# MCU098_06_XDS110-ET_USB_Power.net
KiCad netlist of a schematic drawn in Altium Designer
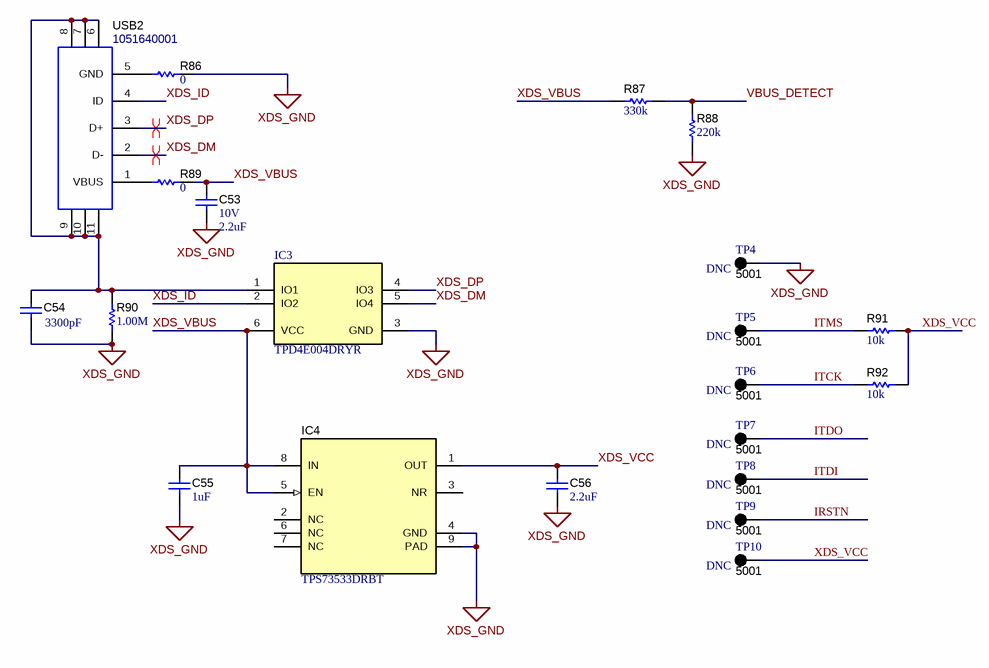
[diagram p0: MCU098_06_XDS110-ET_USB_Power.SchDoc]

(export (version "E")
  (design (tool "Eeschema 10.0.6"))
  (components
    (comp (ref "C53")
      (value "C0603C225K8PACTU")
      (footprint "0603")
      (description "CAP, CERM, 2.2 uF, 10 V, +/- 10%, X5R, 0603")
      (fields
        (field (name "MANUFACTURER") "Kemet")
        (field (name "VDC_V") "10V")
        (field (name "VALUEDISPLAYED") "2.2uF")
        (field (name "PUBLISHER") "Texas Instruments")
      )
      (libsource (lib "Altium Vault - TI") (part "Capacitor"))
    )
    (comp (ref "C54")
      (value "GRM155R71H332KA01D")
      (footprint "0402")
      (description "CAP, CERM, 3300 pF, 50 V, +/- 10%, X7R, 0402")
      (fields
        (field (name "MANUFACTURER") "MuRata")
        (field (name "VALUEDISPLAYED") "3300pF")
        (field (name "PUBLISHER") "Texas Instruments")
      )
      (libsource (lib "Altium Vault - TI") (part "Capacitor"))
    )
    (comp (ref "C55")
      (value "C1005X5R1E105K050BC")
      (footprint "0402")
      (description "CAP, CERM, 1 uF, 25 V, +/- 10%, X5R, 0402")
      (fields
        (field (name "MANUFACTURER") "TDK")
        (field (name "VALUEDISPLAYED") "1uF")
        (field (name "PUBLISHER") "Texas Instruments")
      )
      (libsource (lib "Altium Vault - TI") (part "Capacitor"))
    )
    (comp (ref "C56")
      (value "GRM155R60J225KE95D")
      (footprint "0402")
      (description "CAP, CERM, 2.2 uF, 6.3 V, +/- 10%, X5R, 0402")
      (fields
        (field (name "MANUFACTURER") "MuRata")
        (field (name "VALUEDISPLAYED") "2.2uF")
        (field (name "PUBLISHER") "Texas Instruments")
      )
      (libsource (lib "Altium Vault - TI") (part "Capacitor"))
    )
    (comp (ref "IC3")
      (value "TPD4E004DRYR")
      (footprint "DRY0006A")
      (fields (field (name "MANUFACTURER") "Texas Instruments") (field (name "PARTNUMBER") "TPD4E004DRYR"))
      (libsource (lib "Altium Vault - TI") (part "TI-TPD4E004-SON_DRY-6"))
    )
    (comp (ref "IC4")
      (value "TPS73533DRBT")
      (footprint "DRB0008A")
      (fields (field (name "MANUFACTURER") "Texas Instruments") (field (name "PARTNUMBER") "TPS73533DRBT"))
      (libsource (lib "Altium Vault - TI") (part "TPS735xxDRB"))
    )
    (comp (ref "R86")
      (value "RC0603JR-070RL")
      (footprint "0603")
      (description "RES, 0, 5%, 0.1 W, 0603")
      (fields (field (name "MANUFACTURER") "Yageo") (field (name "VALUEDISPLAYED") "0"))
      (libsource (lib "Altium Vault - TI") (part "Resistor"))
    )
    (comp (ref "R87")
      (value "RC0402FR-07330KL")
      (footprint "0402")
      (description "RES, 330 k, 1%, 0.0625 W, 0402")
      (fields
        (field (name "MANUFACTURER") "Yageo America")
        (field (name "VALUEDISPLAYED") "330k")
        (field (name "PUBLISHER") "Texas Instruments")
      )
      (libsource (lib "Altium Vault - TI") (part "Resistor"))
    )
    (comp (ref "R88")
      (value "RC0402FR-07220KL")
      (footprint "0402")
      (description "RES, 220 k, 1%, 0.0625 W, 0402")
      (fields
        (field (name "MANUFACTURER") "Yageo America")
        (field (name "VALUEDISPLAYED") "220k")
        (field (name "PUBLISHER") "Texas Instruments")
      )
      (libsource (lib "Altium Vault - TI") (part "Resistor"))
    )
    (comp (ref "R89")
      (value "RC0603JR-070RL")
      (footprint "0603")
      (description "RES, 0, 5%, 0.1 W, 0603")
      (fields (field (name "MANUFACTURER") "Yageo") (field (name "VALUEDISPLAYED") "0"))
      (libsource (lib "Altium Vault - TI") (part "Resistor"))
    )
    (comp (ref "R90")
      (value "CRCW04021M00FKED")
      (footprint "0402")
      (description "RES, 1.00 M, 1%, 0.063 W, 0402")
      (fields
        (field (name "MANUFACTURER") "Vishay-Dale")
        (field (name "VALUEDISPLAYED") "1.00M")
        (field (name "PUBLISHER") "Texas Instruments")
      )
      (libsource (lib "Altium Vault - TI") (part "Resistor"))
    )
    (comp (ref "R91")
      (value "CRCW040210K0JNED")
      (footprint "0402")
      (description "RES, 10 k, 5%, 0.063 W, 0402")
      (fields
        (field (name "MANUFACTURER") "Vishay-Dale")
        (field (name "VALUEDISPLAYED") "10k")
        (field (name "PUBLISHER") "Texas Instruments")
      )
      (libsource (lib "Altium Vault - TI") (part "Resistor"))
    )
    (comp (ref "R92")
      (value "CRCW040210K0JNED")
      (footprint "0402")
      (description "RES, 10 k, 5%, 0.063 W, 0402")
      (fields
        (field (name "MANUFACTURER") "Vishay-Dale")
        (field (name "VALUEDISPLAYED") "10k")
        (field (name "PUBLISHER") "Texas Instruments")
      )
      (libsource (lib "Altium Vault - TI") (part "Resistor"))
    )
    (comp (ref "TP4")
      (value "5001")
      (footprint "Keystone5001")
      (description "Test Point, Miniature, Black, TH")
      (fields
        (field (name "MANUFACTURER") "Keystone")
        (field (name "DISPLAY") "DNC")
        (field (name "PUBLISHER") "Texas Instruments")
      )
      (libsource (lib "Altium Vault - TI") (part "5001"))
    )
    (comp (ref "TP5")
      (value "5001")
      (footprint "Keystone5001")
      (description "Test Point, Miniature, Black, TH")
      (fields
        (field (name "MANUFACTURER") "Keystone")
        (field (name "DISPALY") "DNC")
        (field (name "PUBLISHER") "Texas Instruments")
      )
      (libsource (lib "Altium Vault - TI") (part "5001"))
    )
    (comp (ref "TP6")
      (value "5001")
      (footprint "Keystone5001")
      (description "Test Point, Miniature, Black, TH")
      (fields
        (field (name "MANUFACTURER") "Keystone")
        (field (name "DISPALY") "DNC")
        (field (name "PUBLISHER") "Texas Instruments")
      )
      (libsource (lib "Altium Vault - TI") (part "5001"))
    )
    (comp (ref "TP7")
      (value "5001")
      (footprint "Keystone5001")
      (description "Test Point, Miniature, Black, TH")
      (fields
        (field (name "MANUFACTURER") "Keystone")
        (field (name "DISPALY") "DNC")
        (field (name "PUBLISHER") "Texas Instruments")
      )
      (libsource (lib "Altium Vault - TI") (part "5001"))
    )
    (comp (ref "TP8")
      (value "5001")
      (footprint "Keystone5001")
      (description "Test Point, Miniature, Black, TH")
      (fields
        (field (name "MANUFACTURER") "Keystone")
        (field (name "DISPALY") "DNC")
        (field (name "PUBLISHER") "Texas Instruments")
      )
      (libsource (lib "Altium Vault - TI") (part "5001"))
    )
    (comp (ref "TP9")
      (value "5001")
      (footprint "Keystone5001")
      (description "Test Point, Miniature, Black, TH")
      (fields
        (field (name "MANUFACTURER") "Keystone")
        (field (name "DISPALY") "DNC")
        (field (name "PUBLISHER") "Texas Instruments")
      )
      (libsource (lib "Altium Vault - TI") (part "5001"))
    )
    (comp (ref "TP10")
      (value "5001")
      (footprint "Keystone5001")
      (description "Test Point, Miniature, Black, TH")
      (fields
        (field (name "MANUFACTURER") "Keystone")
        (field (name "DISPALY") "DNC")
        (field (name "PUBLISHER") "Texas Instruments")
      )
      (libsource (lib "Altium Vault - TI") (part "5001"))
    )
    (comp (ref "USB2")
      (value "1051640001")
      (footprint "Molex_1051640001")
      (description "Receptacle, USB 2.0, Micro B, 5 Position, R/A, SMT")
      (fields (field (name "MANUFACTURER") "Molex") (field (name "PUBLISHER") "Texas Instruments"))
      (libsource (lib "Altium Vault - TI") (part "CONN_USB_MicroMini_6Shld"))
    )
  )
  (nets
    (net (code "1") (name "/IRSTN") (class "Default") (node (ref "TP9") (pin "1") (pintype "passive")))
    (net (code "2") (name "/ITCK") (class "Default")
      (node (ref "R92") (pin "2") (pinfunction "2_2") (pintype "passive"))
      (node (ref "TP6") (pin "1") (pintype "passive"))
    )
    (net (code "3") (name "/ITDI") (class "Default") (node (ref "TP8") (pin "1") (pintype "passive")))
    (net (code "4") (name "/ITDO") (class "Default") (node (ref "TP7") (pin "1") (pintype "passive")))
    (net (code "5") (name "/ITMS") (class "Default")
      (node (ref "R91") (pin "2") (pinfunction "2_2") (pintype "passive"))
      (node (ref "TP5") (pin "1") (pintype "passive"))
    )
    (net (code "6") (name "/VBUS_DETECT") (class "Default")
      (node (ref "R87") (pin "2") (pinfunction "2_2") (pintype "passive"))
      (node (ref "R88") (pin "2") (pinfunction "2_2") (pintype "passive"))
    )
    (net (code "7") (name "/XDS_DM") (class "Default")
      (node (ref "IC3") (pin "5") (pinfunction "IO4_5") (pintype "passive"))
      (node (ref "USB2") (pin "2") (pinfunction "D-_2") (pintype "passive"))
    )
    (net (code "8") (name "/XDS_DP") (class "Default")
      (node (ref "IC3") (pin "4") (pinfunction "IO3_4") (pintype "passive"))
      (node (ref "USB2") (pin "3") (pinfunction "D+_3") (pintype "passive"))
    )
    (net (code "9") (name "/XDS_ID") (class "Default")
      (node (ref "IC3") (pin "2") (pinfunction "IO2_2") (pintype "passive"))
      (node (ref "USB2") (pin "4") (pinfunction "ID_4") (pintype "passive"))
    )
    (net (code "10") (name "/XDS_VBUS") (class "Default")
      (node (ref "C53") (pin "1") (pinfunction "1_1") (pintype "passive"))
      (node (ref "C55") (pin "1") (pinfunction "1_1") (pintype "passive"))
      (node (ref "IC3") (pin "6") (pinfunction "VCC_6") (pintype "power_in"))
      (node (ref "IC4") (pin "5") (pinfunction "EN_5") (pintype "input"))
      (node (ref "IC4") (pin "8") (pinfunction "IN_8") (pintype "power_in"))
      (node (ref "R87") (pin "1") (pinfunction "1_1") (pintype "passive"))
      (node (ref "R89") (pin "2") (pinfunction "2_2") (pintype "passive"))
    )
    (net (code "11") (name "/XDS_VCC") (class "Default")
      (node (ref "C56") (pin "1") (pinfunction "1_1") (pintype "passive"))
      (node (ref "IC4") (pin "1") (pinfunction "OUT_1") (pintype "power_in"))
      (node (ref "R91") (pin "1") (pinfunction "1_1") (pintype "passive"))
      (node (ref "R92") (pin "1") (pinfunction "1_1") (pintype "passive"))
      (node (ref "TP10") (pin "1") (pintype "passive"))
    )
    (net (code "12") (name "Net-(IC3-IO1)") (class "Default")
      (node (ref "C54") (pin "1") (pinfunction "1_1") (pintype "passive"))
      (node (ref "IC3") (pin "1") (pinfunction "IO1_1") (pintype "passive"))
      (node (ref "R90") (pin "2") (pinfunction "2_2") (pintype "passive"))
      (node (ref "USB2") (pin "10") (pinfunction "10_10") (pintype "passive"))
      (node (ref "USB2") (pin "11") (pinfunction "11_11") (pintype "passive"))
      (node (ref "USB2") (pin "6") (pinfunction "6_6") (pintype "passive"))
      (node (ref "USB2") (pin "7") (pinfunction "7_7") (pintype "passive"))
      (node (ref "USB2") (pin "8") (pinfunction "8_8") (pintype "passive"))
      (node (ref "USB2") (pin "9") (pinfunction "9_9") (pintype "passive"))
    )
    (net (code "13") (name "Net-(USB2-GND)") (class "Default")
      (node (ref "R86") (pin "1") (pinfunction "1_1") (pintype "passive"))
      (node (ref "USB2") (pin "5") (pinfunction "GND_5") (pintype "passive"))
    )
    (net (code "14") (name "Net-(USB2-VBUS)") (class "Default")
      (node (ref "R89") (pin "1") (pinfunction "1_1") (pintype "passive"))
      (node (ref "USB2") (pin "1") (pinfunction "VBUS_1") (pintype "passive"))
    )
    (net (code "15") (name "XDS_GND") (class "Default")
      (node (ref "C53") (pin "2") (pinfunction "2_2") (pintype "passive"))
      (node (ref "C54") (pin "2") (pinfunction "2_2") (pintype "passive"))
      (node (ref "C55") (pin "2") (pinfunction "2_2") (pintype "passive"))
      (node (ref "C56") (pin "2") (pinfunction "2_2") (pintype "passive"))
      (node (ref "IC3") (pin "3") (pinfunction "GND_3") (pintype "power_in"))
      (node (ref "IC4") (pin "4") (pinfunction "GND_4") (pintype "power_in"))
      (node (ref "IC4") (pin "9") (pinfunction "PAD_9") (pintype "power_in"))
      (node (ref "R86") (pin "2") (pinfunction "2_2") (pintype "passive"))
      (node (ref "R88") (pin "1") (pinfunction "1_1") (pintype "passive"))
      (node (ref "R90") (pin "1") (pinfunction "1_1") (pintype "passive"))
      (node (ref "TP4") (pin "1") (pintype "passive"))
    )
    (net (code "16") (name "unconnected-(IC4-NC-Pad2)") (class "Default")
      (node (ref "IC4") (pin "2") (pinfunction "NC_2") (pintype "passive"))
    )
    (net (code "17") (name "unconnected-(IC4-NC-Pad6)") (class "Default")
      (node (ref "IC4") (pin "6") (pinfunction "NC_6") (pintype "passive"))
    )
    (net (code "18") (name "unconnected-(IC4-NC-Pad7)") (class "Default")
      (node (ref "IC4") (pin "7") (pinfunction "NC_7") (pintype "passive"))
    )
    (net (code "19") (name "unconnected-(IC4-NR-Pad3)") (class "Default")
      (node (ref "IC4") (pin "3") (pinfunction "NR_3") (pintype "passive"))
    )
  )
)
